# 05_-_IMU.net
KiCad netlist of a schematic drawn in Altium Designer
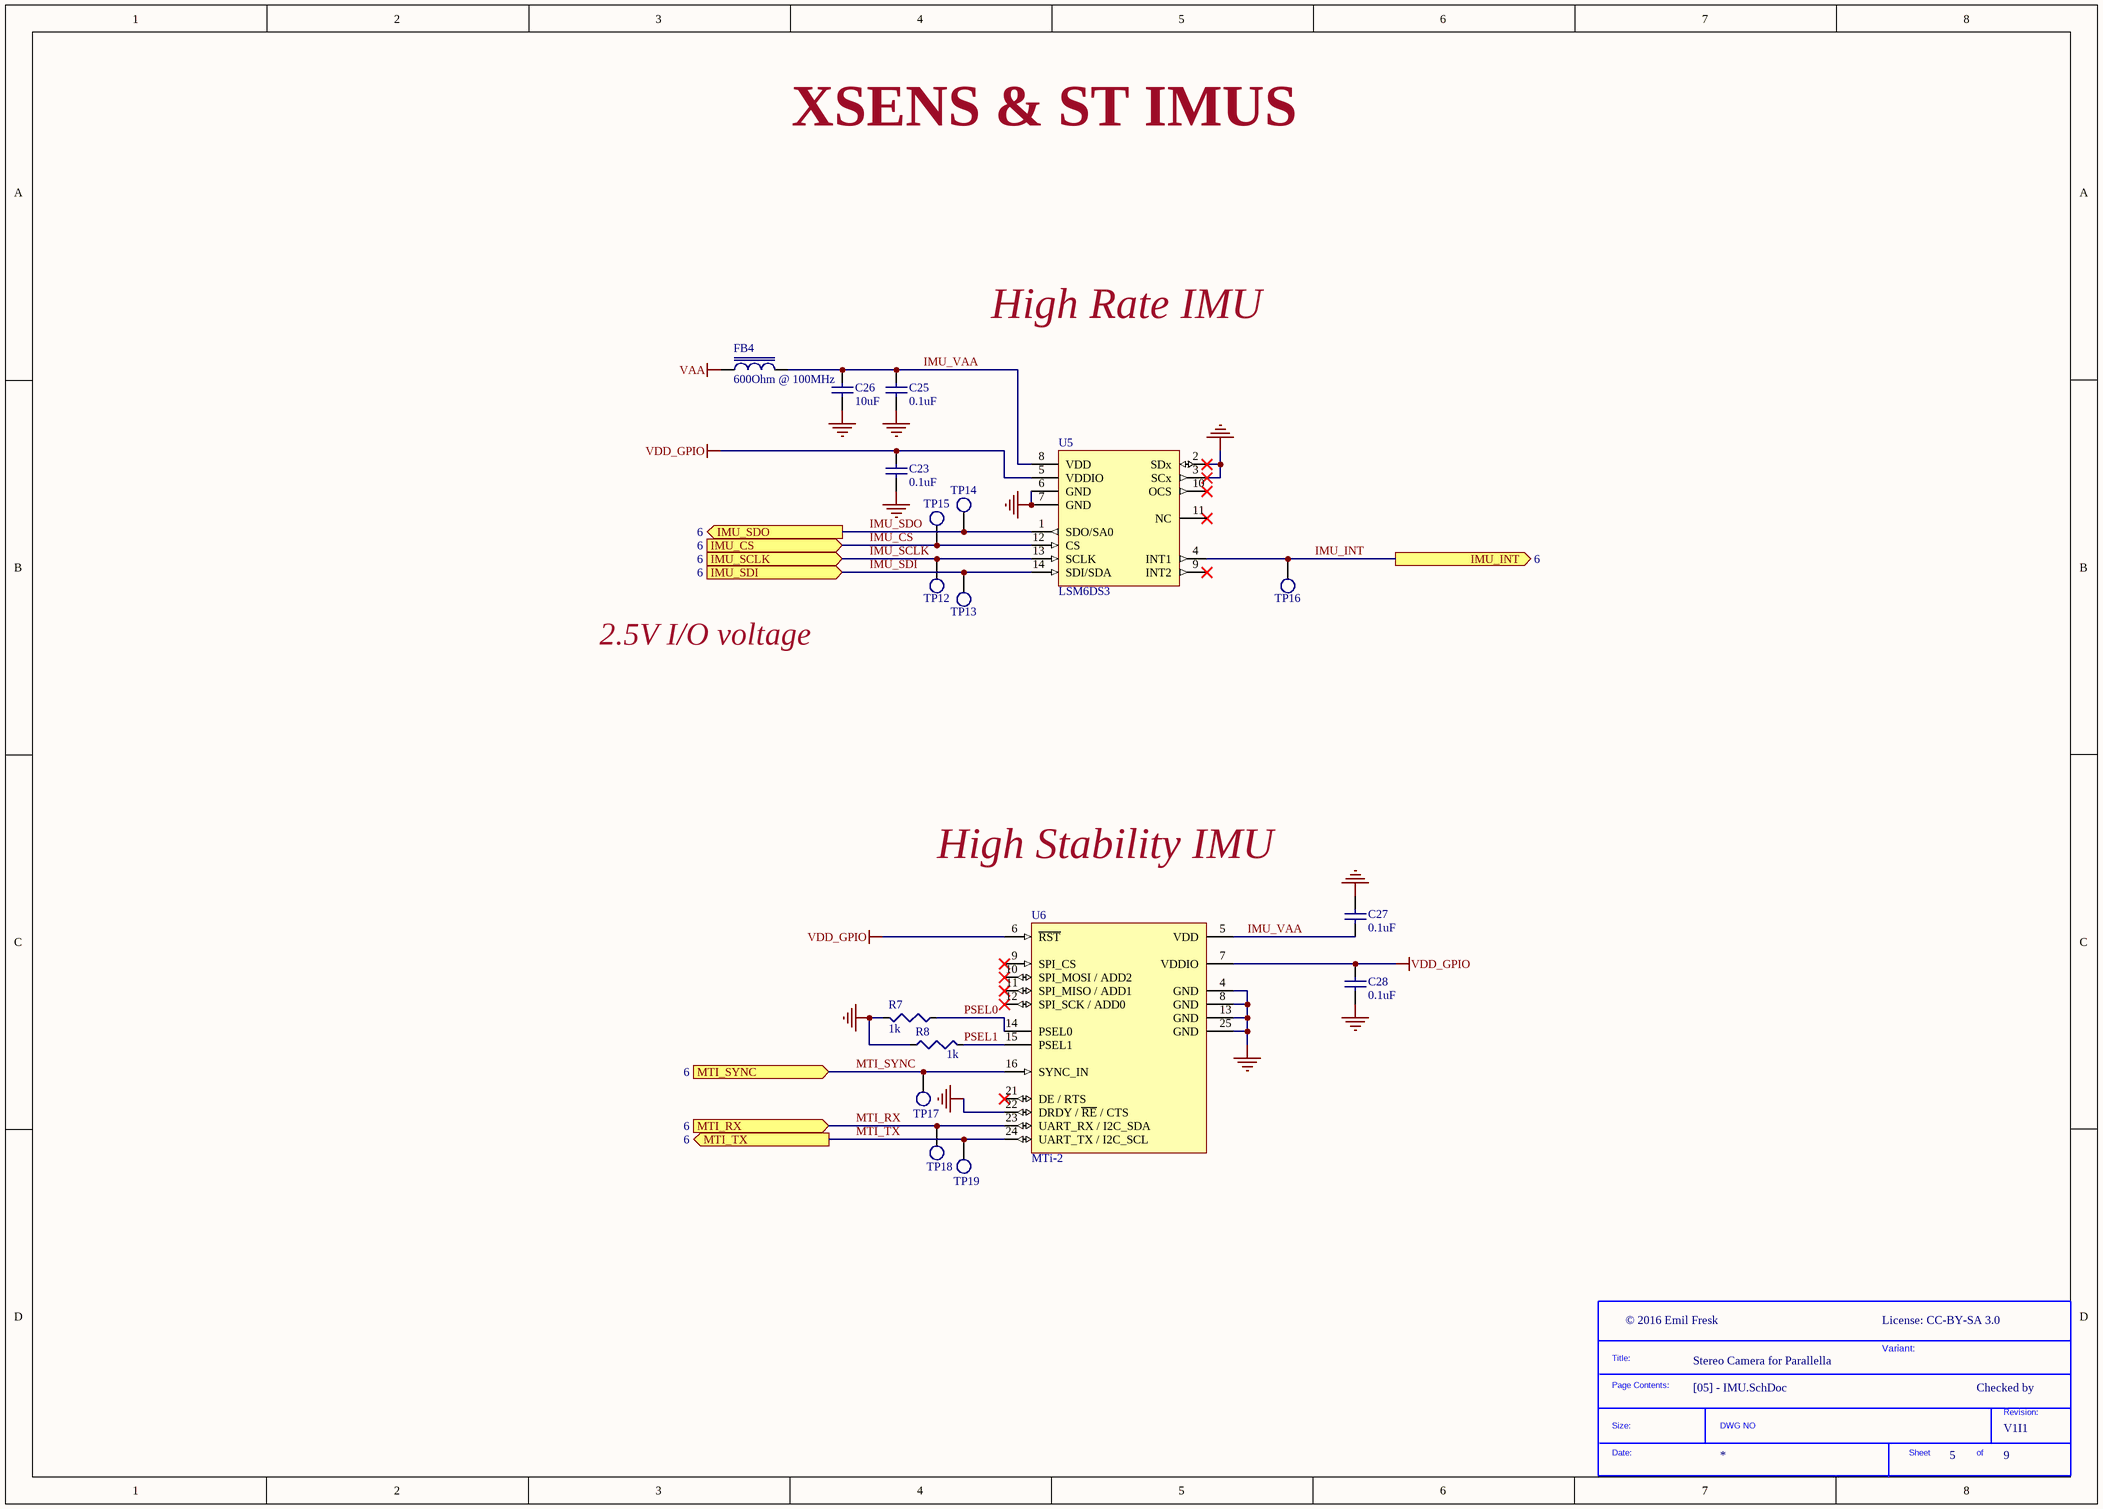
[diagram p0: [05] - IMU.SchDoc]

(export (version "E")
  (design (tool "Eeschema 10.0.6"))
  (components
    (comp (ref "C23")
      (value "0.1uF")
      (footprint "C0603L")
      (description "CAP CER 0.1UF 50V 10% X7R 0603")
      (fields
        (field (name "MANUFACTURER") "Murata Electronics North America")
        (field (name "MANUFACTURER PART NUMBER") "GRM188R71H104KA93J")
      )
      (libsource (lib "Capacitors") (part "GRM188R71H104KA93J"))
    )
    (comp (ref "C25")
      (value "0.1uF")
      (footprint "C0603L")
      (description "CAP CER 0.1UF 50V 10% X7R 0603")
      (fields
        (field (name "MANUFACTURER") "Murata Electronics North America")
        (field (name "MANUFACTURER PART NUMBER") "GRM188R71H104KA93J")
      )
      (libsource (lib "Capacitors") (part "GRM188R71H104KA93J"))
    )
    (comp (ref "C26")
      (value "10uF")
      (footprint "C0603L")
      (description "CAP CER 10UF 16V 20% X5R 0603")
      (fields
        (field (name "MANUFACTURER") "Murata Electronics North America")
        (field (name "MANUFACTURER PART NUMBER") "GRM188R61C106MA73D")
      )
      (libsource (lib "Capacitors") (part "GRM188R61C106MA73D"))
    )
    (comp (ref "C27")
      (value "0.1uF")
      (footprint "C0603L")
      (description "CAP CER 0.1UF 50V 10% X7R 0603")
      (fields
        (field (name "MANUFACTURER") "Murata Electronics North America")
        (field (name "MANUFACTURER PART NUMBER") "GRM188R71H104KA93J")
      )
      (libsource (lib "Capacitors") (part "GRM188R71H104KA93J"))
    )
    (comp (ref "C28")
      (value "0.1uF")
      (footprint "C0603L")
      (description "CAP CER 0.1UF 50V 10% X7R 0603")
      (fields
        (field (name "MANUFACTURER") "Murata Electronics North America")
        (field (name "MANUFACTURER PART NUMBER") "GRM188R71H104KA93J")
      )
      (libsource (lib "Capacitors") (part "GRM188R71H104KA93J"))
    )
    (comp (ref "FB4")
      (value "600Ohm @ 100MHz")
      (footprint "R0603L")
      (description "FERRITE CHIP BEAD 600 OHM SMD")
      (fields
        (field (name "MANUFACTURER") "TDK Corporation")
        (field (name "MANUFACTURER PART NUMBER") "MPZ1608S601ATA00")
      )
      (libsource (lib "Inductors") (part "MPZ1608S601ATA00"))
    )
    (comp (ref "R7")
      (value "1k")
      (footprint "R0603L")
      (description "RES SMD 1K OHM 1% 1/10W 0603")
      (fields
        (field (name "MANUFACTURER") "Vishay Dale")
        (field (name "MANUFACTURER PART NUMBER") "CRCW06031K00FKEA")
      )
      (libsource (lib "Resistors") (part "CRCW06031K00FKEA"))
    )
    (comp (ref "R8")
      (value "1k")
      (footprint "R0603L")
      (description "RES SMD 1K OHM 1% 1/10W 0603")
      (fields
        (field (name "MANUFACTURER") "Vishay Dale")
        (field (name "MANUFACTURER PART NUMBER") "CRCW06031K00FKEA")
      )
      (libsource (lib "Resistors") (part "CRCW06031K00FKEA"))
    )
    (comp (ref "TP12")
      (value "TestPoint")
      (footprint "TestPoint_1.5mm")
      (libsource (lib "TestPoint") (part "TestPoint"))
    )
    (comp (ref "TP13")
      (value "TestPoint")
      (footprint "TestPoint_1.5mm")
      (libsource (lib "TestPoint") (part "TestPoint"))
    )
    (comp (ref "TP14")
      (value "TestPoint")
      (footprint "TestPoint_1.5mm")
      (libsource (lib "TestPoint") (part "TestPoint"))
    )
    (comp (ref "TP15")
      (value "TestPoint")
      (footprint "TestPoint_1.5mm")
      (libsource (lib "TestPoint") (part "TestPoint"))
    )
    (comp (ref "TP16")
      (value "TestPoint")
      (footprint "TestPoint_1.5mm")
      (libsource (lib "TestPoint") (part "TestPoint"))
    )
    (comp (ref "TP17")
      (value "TestPoint")
      (footprint "TestPoint_1.5mm")
      (libsource (lib "TestPoint") (part "TestPoint"))
    )
    (comp (ref "TP18")
      (value "TestPoint")
      (footprint "TestPoint_1.5mm")
      (libsource (lib "TestPoint") (part "TestPoint"))
    )
    (comp (ref "TP19")
      (value "TestPoint")
      (footprint "TestPoint_1.5mm")
      (libsource (lib "TestPoint") (part "TestPoint"))
    )
    (comp (ref "U5")
      (value "LSM6DS3")
      (footprint "LGA14-N")
      (description "IC MOD 3D ACC/GYRO INEMO 14VFLGA")
      (fields
        (field (name "MANUFACTURER") "STMicroelectronics")
        (field (name "MANUFACTURER PART NUMBER") "LSM6DS3TR")
      )
      (libsource (lib "ST") (part "LSM6DS3TR"))
    )
    (comp (ref "U6") (value "MTi-2") (footprint "MTi-1") (libsource (lib "Xsens") (part "MTi-1")))
  )
  (nets
    (net (code "1") (name "/IMU_CS") (class "Default")
      (node (ref "TP15") (pin "1") (pinfunction "1_1") (pintype "passive"))
      (node (ref "U5") (pin "12") (pinfunction "CS_12") (pintype "input"))
    )
    (net (code "2") (name "/IMU_INT") (class "Default")
      (node (ref "TP16") (pin "1") (pinfunction "1_1") (pintype "passive"))
      (node (ref "U5") (pin "4") (pinfunction "INT1_4") (pintype "output"))
    )
    (net (code "3") (name "/IMU_SCLK") (class "Default")
      (node (ref "TP12") (pin "1") (pinfunction "1_1") (pintype "passive"))
      (node (ref "U5") (pin "13") (pinfunction "SCLK_13") (pintype "input"))
    )
    (net (code "4") (name "/IMU_SDI") (class "Default")
      (node (ref "TP13") (pin "1") (pinfunction "1_1") (pintype "passive"))
      (node (ref "U5") (pin "14") (pinfunction "SDI/SDA_14") (pintype "input"))
    )
    (net (code "5") (name "/IMU_SDO") (class "Default")
      (node (ref "TP14") (pin "1") (pinfunction "1_1") (pintype "passive"))
      (node (ref "U5") (pin "1") (pinfunction "SDO/SA0_1") (pintype "output"))
    )
    (net (code "6") (name "/IMU_VAA") (class "Default")
      (node (ref "C25") (pin "1") (pinfunction "1_1") (pintype "passive"))
      (node (ref "C26") (pin "1") (pinfunction "1_1") (pintype "passive"))
      (node (ref "C27") (pin "2") (pinfunction "2_2") (pintype "passive"))
      (node (ref "FB4") (pin "2") (pinfunction "2_2") (pintype "passive"))
      (node (ref "U5") (pin "8") (pinfunction "VDD_8") (pintype "power_in"))
      (node (ref "U6") (pin "5") (pinfunction "VDD_5") (pintype "power_in"))
    )
    (net (code "7") (name "/MTI_RX") (class "Default")
      (node (ref "TP18") (pin "1") (pinfunction "1_1") (pintype "passive"))
      (node (ref "U6") (pin "23") (pinfunction "UART_RX_/_I2C_SDA_23") (pintype "bidirectional"))
    )
    (net (code "8") (name "/MTI_SYNC") (class "Default")
      (node (ref "TP17") (pin "1") (pinfunction "1_1") (pintype "passive"))
      (node (ref "U6") (pin "16") (pinfunction "SYNC_IN_16") (pintype "input"))
    )
    (net (code "9") (name "/MTI_TX") (class "Default")
      (node (ref "TP19") (pin "1") (pinfunction "1_1") (pintype "passive"))
      (node (ref "U6") (pin "24") (pinfunction "UART_TX_/_I2C_SCL_24") (pintype "bidirectional"))
    )
    (net (code "10") (name "/PSEL0") (class "Default")
      (node (ref "R7") (pin "1") (pinfunction "1_1") (pintype "passive"))
      (node (ref "U6") (pin "14") (pinfunction "PSEL0_14") (pintype "passive"))
    )
    (net (code "11") (name "/PSEL1") (class "Default")
      (node (ref "R8") (pin "2") (pinfunction "2_2") (pintype "passive"))
      (node (ref "U6") (pin "15") (pinfunction "PSEL1_15") (pintype "passive"))
    )
    (net (code "12") (name "GND") (class "Default")
      (node (ref "C23") (pin "2") (pinfunction "2_2") (pintype "passive"))
      (node (ref "C25") (pin "2") (pinfunction "2_2") (pintype "passive"))
      (node (ref "C26") (pin "2") (pinfunction "2_2") (pintype "passive"))
      (node (ref "C27") (pin "1") (pinfunction "1_1") (pintype "passive"))
      (node (ref "C28") (pin "2") (pinfunction "2_2") (pintype "passive"))
      (node (ref "R7") (pin "2") (pinfunction "2_2") (pintype "passive"))
      (node (ref "R8") (pin "1") (pinfunction "1_1") (pintype "passive"))
      (node (ref "U5") (pin "2") (pinfunction "SDx_2") (pintype "bidirectional"))
      (node (ref "U5") (pin "3") (pinfunction "SCx_3") (pintype "output"))
      (node (ref "U5") (pin "6") (pinfunction "GND_6") (pintype "power_in"))
      (node (ref "U5") (pin "7") (pinfunction "GND_7") (pintype "power_in"))
      (node (ref "U6") (pin "13") (pinfunction "GND_13") (pintype "power_in"))
      (node (ref "U6") (pin "22") (pinfunction "DRDY_/_~{RE}_/_CTS_22") (pintype "bidirectional"))
      (node (ref "U6") (pin "25") (pinfunction "GND_25") (pintype "power_in"))
      (node (ref "U6") (pin "4") (pinfunction "GND_4") (pintype "power_in"))
      (node (ref "U6") (pin "8") (pinfunction "GND_8") (pintype "power_in"))
    )
    (net (code "13") (name "VAA") (class "Default")
      (node (ref "FB4") (pin "1") (pinfunction "1_1") (pintype "passive"))
    )
    (net (code "14") (name "VDD_GPIO") (class "Default")
      (node (ref "C23") (pin "1") (pinfunction "1_1") (pintype "passive"))
      (node (ref "C28") (pin "1") (pinfunction "1_1") (pintype "passive"))
      (node (ref "U5") (pin "5") (pinfunction "VDDIO_5") (pintype "power_in"))
      (node (ref "U6") (pin "6") (pinfunction "~{RST}_6") (pintype "input"))
      (node (ref "U6") (pin "7") (pinfunction "VDDIO_7") (pintype "power_in"))
    )
    (net (code "15") (name "unconnected-(U5-INT2-Pad9)") (class "Default")
      (node (ref "U5") (pin "9") (pinfunction "INT2_9") (pintype "output+no_connect"))
    )
    (net (code "16") (name "unconnected-(U5-NC-Pad11)") (class "Default")
      (node (ref "U5") (pin "11") (pinfunction "NC_11") (pintype "passive+no_connect"))
    )
    (net (code "17") (name "unconnected-(U5-OCS-Pad10)") (class "Default")
      (node (ref "U5") (pin "10") (pinfunction "OCS_10") (pintype "output+no_connect"))
    )
    (net (code "18") (name "unconnected-(U6-DE_{slash}_RTS-Pad21)") (class "Default")
      (node (ref "U6") (pin "21") (pinfunction "DE_/_RTS_21") (pintype "bidirectional+no_connect"))
    )
    (net (code "19") (name "unconnected-(U6-SPI_CS-Pad9)") (class "Default")
      (node (ref "U6") (pin "9") (pinfunction "SPI_CS_9") (pintype "input+no_connect"))
    )
    (net (code "20") (name "unconnected-(U6-SPI_MISO_{slash}_ADD1-Pad11)") (class "Default")
      (node (ref "U6") (pin "11") (pinfunction "SPI_MISO_/_ADD1_11") (pintype "bidirectional+no_connect"))
    )
    (net (code "21") (name "unconnected-(U6-SPI_MOSI_{slash}_ADD2-Pad10)") (class "Default")
      (node (ref "U6") (pin "10") (pinfunction "SPI_MOSI_/_ADD2_10") (pintype "bidirectional+no_connect"))
    )
    (net (code "22") (name "unconnected-(U6-SPI_SCK_{slash}_ADD0-Pad12)") (class "Default")
      (node (ref "U6") (pin "12") (pinfunction "SPI_SCK_/_ADD0_12") (pintype "bidirectional+no_connect"))
    )
  )
)
